# SignalAndKeyController.net
KiCad netlist of a schematic drawn in Altium Designer
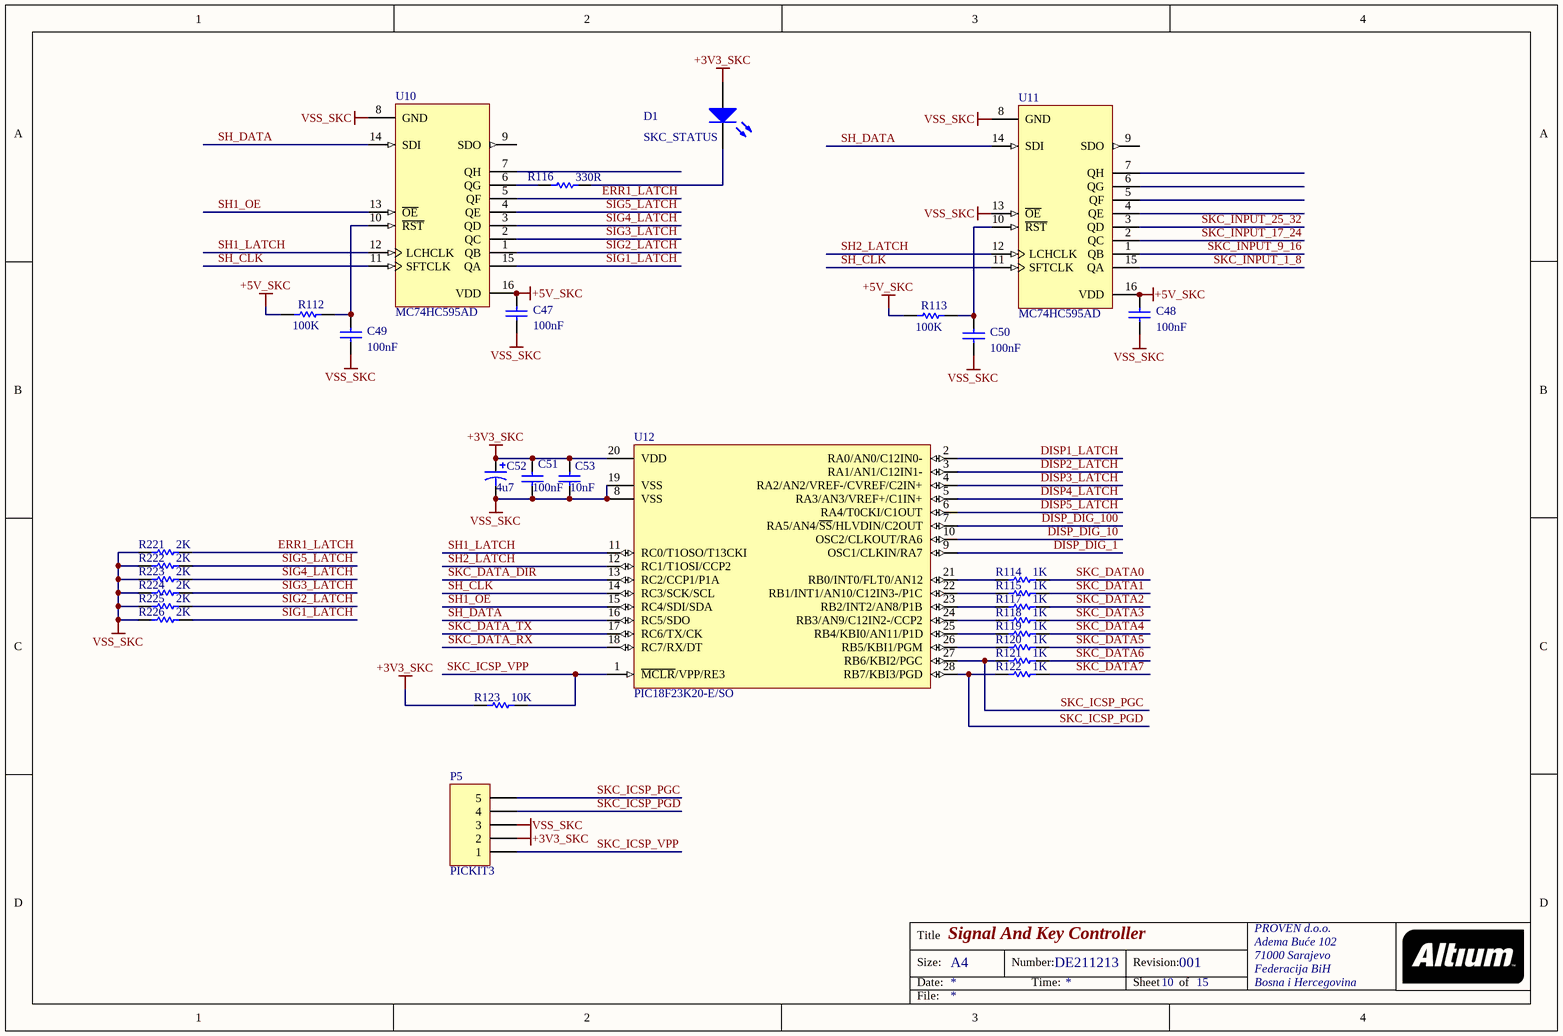
[diagram p0: SignalAndKeyController.SchDoc]

(export (version "E")
  (design (tool "Eeschema 10.0.6"))
  (components
    (comp (ref "C47")
      (value "100nF")
      (footprint "1206")
      (description "Ceramic Chip Capacitor - Standard")
      (fields (field (name "PUBLISHER") "Altium Limited"))
      (libsource (lib "KEMET Chip Capacitor") (part "C1206"))
    )
    (comp (ref "C48")
      (value "100nF")
      (footprint "1206")
      (description "Ceramic Chip Capacitor - Standard")
      (fields (field (name "PUBLISHER") "Altium Limited"))
      (libsource (lib "KEMET Chip Capacitor") (part "C1206"))
    )
    (comp (ref "C49")
      (value "100nF")
      (footprint "1206")
      (description "Ceramic Chip Capacitor - Standard")
      (fields (field (name "PUBLISHER") "Altium Limited"))
      (libsource (lib "KEMET Chip Capacitor") (part "C1206"))
    )
    (comp (ref "C50")
      (value "100nF")
      (footprint "1206")
      (description "Ceramic Chip Capacitor - Standard")
      (fields (field (name "PUBLISHER") "Altium Limited"))
      (libsource (lib "KEMET Chip Capacitor") (part "C1206"))
    )
    (comp (ref "C51")
      (value "100nF")
      (footprint "1206")
      (description "Ceramic Chip Capacitor - Standard")
      (fields (field (name "PUBLISHER") "Altium Limited"))
      (libsource (lib "KEMET Chip Capacitor") (part "C1206"))
    )
    (comp (ref "C52")
      (value "4u7")
      (footprint "C")
      (description "Solid Aluminum Capacitor with Organic Semiconductor Electrolyte: 4.7uF, 25V, Bulk Pack")
      (fields (field (name "PUBLISHER") "Altium Limited"))
      (libsource (lib "Vishay Electrolytic Radial-Lead Capacitor") (part "94SC475X0025CBP"))
    )
    (comp (ref "C53")
      (value "10nF")
      (footprint "0805")
      (description "Ceramic Chip Capacitor - Standard")
      (fields (field (name "PUBLISHER") "Altium Limited"))
      (libsource (lib "KEMET Chip Capacitor") (part "C0805"))
    )
    (comp (ref "D1")
      (value "SKC_STATUS")
      (footprint "2.0X1.25X0.8")
      (description "SMT Top Mount Chip LED, Amber")
      (fields (field (name "PUBLISHER") "Altium Limited"))
      (libsource (lib "Avago Optoelectronic LED") (part "HSMA-S670"))
    )
    (comp (ref "P5")
      (value "PICKIT3")
      (footprint "HDR1X5")
      (description "Header, 5-Pin")
      (fields (field (name "PUBLISHER") "Altium Limited"))
      (libsource (lib "Miscellaneous Connectors") (part "Header 5"))
    )
    (comp (ref "R112")
      (value "100K")
      (footprint "ERA-0603")
      (fields (field (name "PUBLISHER") "Altium Limited"))
      (libsource (lib "Panasonic Resistor") (part "ERA3Y"))
    )
    (comp (ref "R113")
      (value "100K")
      (footprint "ERA-0603")
      (fields (field (name "PUBLISHER") "Altium Limited"))
      (libsource (lib "Panasonic Resistor") (part "ERA3Y"))
    )
    (comp (ref "R114")
      (value "1K")
      (footprint "ERA-0603")
      (fields (field (name "PUBLISHER") "Altium Limited"))
      (libsource (lib "Panasonic Resistor") (part "ERA3Y"))
    )
    (comp (ref "R115")
      (value "1K")
      (footprint "ERA-0603")
      (fields (field (name "PUBLISHER") "Altium Limited"))
      (libsource (lib "Panasonic Resistor") (part "ERA3Y"))
    )
    (comp (ref "R116")
      (value "330R")
      (footprint "ERA-0603")
      (fields (field (name "PUBLISHER") "Altium Limited"))
      (libsource (lib "Panasonic Resistor") (part "ERA3Y"))
    )
    (comp (ref "R117")
      (value "1K")
      (footprint "ERA-0603")
      (fields (field (name "PUBLISHER") "Altium Limited"))
      (libsource (lib "Panasonic Resistor") (part "ERA3Y"))
    )
    (comp (ref "R118")
      (value "1K")
      (footprint "ERA-0603")
      (fields (field (name "PUBLISHER") "Altium Limited"))
      (libsource (lib "Panasonic Resistor") (part "ERA3Y"))
    )
    (comp (ref "R119")
      (value "1K")
      (footprint "ERA-0603")
      (fields (field (name "PUBLISHER") "Altium Limited"))
      (libsource (lib "Panasonic Resistor") (part "ERA3Y"))
    )
    (comp (ref "R120")
      (value "1K")
      (footprint "ERA-0603")
      (fields (field (name "PUBLISHER") "Altium Limited"))
      (libsource (lib "Panasonic Resistor") (part "ERA3Y"))
    )
    (comp (ref "R121")
      (value "1K")
      (footprint "ERA-0603")
      (fields (field (name "PUBLISHER") "Altium Limited"))
      (libsource (lib "Panasonic Resistor") (part "ERA3Y"))
    )
    (comp (ref "R122")
      (value "1K")
      (footprint "ERA-0603")
      (fields (field (name "PUBLISHER") "Altium Limited"))
      (libsource (lib "Panasonic Resistor") (part "ERA3Y"))
    )
    (comp (ref "R123")
      (value "10K")
      (footprint "ERA-0603")
      (fields (field (name "PUBLISHER") "Altium Limited"))
      (libsource (lib "Panasonic Resistor") (part "ERA3Y"))
    )
    (comp (ref "R221")
      (value "2K")
      (footprint "ERA-0603")
      (fields (field (name "PUBLISHER") "Altium Limited"))
      (libsource (lib "Panasonic Resistor") (part "ERA3Y"))
    )
    (comp (ref "R222")
      (value "2K")
      (footprint "ERA-0603")
      (fields (field (name "PUBLISHER") "Altium Limited"))
      (libsource (lib "Panasonic Resistor") (part "ERA3Y"))
    )
    (comp (ref "R223")
      (value "2K")
      (footprint "ERA-0603")
      (fields (field (name "PUBLISHER") "Altium Limited"))
      (libsource (lib "Panasonic Resistor") (part "ERA3Y"))
    )
    (comp (ref "R224")
      (value "2K")
      (footprint "ERA-0603")
      (fields (field (name "PUBLISHER") "Altium Limited"))
      (libsource (lib "Panasonic Resistor") (part "ERA3Y"))
    )
    (comp (ref "R225")
      (value "2K")
      (footprint "ERA-0603")
      (fields (field (name "PUBLISHER") "Altium Limited"))
      (libsource (lib "Panasonic Resistor") (part "ERA3Y"))
    )
    (comp (ref "R226")
      (value "2K")
      (footprint "ERA-0603")
      (fields (field (name "PUBLISHER") "Altium Limited"))
      (libsource (lib "Panasonic Resistor") (part "ERA3Y"))
    )
    (comp (ref "U10")
      (value "MC74HC595AD")
      (footprint "751B-05_N")
      (description "8-Bit Serial-Input/Serial or Prallel-Output Shift Register with Latched 3-State Outputs")
      (fields (field (name "PUBLISHER") "Altium Limited"))
      (libsource (lib "ON Semi Logic Register") (part "MC74HC595AD"))
    )
    (comp (ref "U11")
      (value "MC74HC595AD")
      (footprint "751B-05_N")
      (description "8-Bit Serial-Input/Serial or Prallel-Output Shift Register with Latched 3-State Outputs")
      (fields (field (name "PUBLISHER") "Altium Limited"))
      (libsource (lib "ON Semi Logic Register") (part "MC74HC595AD"))
    )
    (comp (ref "U12")
      (value "PIC18F23K20-E/SO")
      (footprint "SOIC-SO28_N")
      (description "Flash Microcontroller with nanoWatt XLP Technology, 28-pin SOIC, Extended Temperature")
      (fields (field (name "PUBLISHER") "Altium Limited"))
      (libsource (lib "Microchip Microcontroller 8-Bit PIC18") (part "PIC18F23K20-E/SO"))
    )
  )
  (nets
    (net (code "1") (name "+3V3_SKC") (class "Default")
      (node (ref "C51") (pin "2") (pinfunction "2_2") (pintype "passive"))
      (node (ref "C52") (pin "1") (pinfunction "1_1") (pintype "passive"))
      (node (ref "C53") (pin "2") (pinfunction "2_2") (pintype "passive"))
      (node (ref "D1") (pin "1") (pinfunction "A_1") (pintype "passive"))
      (node (ref "P5") (pin "2") (pinfunction "2_2") (pintype "passive"))
      (node (ref "R123") (pin "1") (pinfunction "1_1") (pintype "passive"))
      (node (ref "U12") (pin "20") (pinfunction "VDD_20") (pintype "power_in"))
    )
    (net (code "2") (name "+5V_SKC") (class "Default")
      (node (ref "C47") (pin "2") (pinfunction "2_2") (pintype "passive"))
      (node (ref "C48") (pin "2") (pinfunction "2_2") (pintype "passive"))
      (node (ref "R112") (pin "1") (pinfunction "1_1") (pintype "passive"))
      (node (ref "R113") (pin "1") (pinfunction "1_1") (pintype "passive"))
      (node (ref "U10") (pin "16") (pinfunction "VDD_16") (pintype "power_in"))
      (node (ref "U11") (pin "16") (pinfunction "VDD_16") (pintype "power_in"))
    )
    (net (code "3") (name "/DISP1_LATCH") (class "Default")
      (node (ref "U12") (pin "2") (pinfunction "RA0/AN0/C12IN0-_2") (pintype "bidirectional"))
    )
    (net (code "4") (name "/DISP2_LATCH") (class "Default")
      (node (ref "U12") (pin "3") (pinfunction "RA1/AN1/C12IN1-_3") (pintype "bidirectional"))
    )
    (net (code "5") (name "/DISP3_LATCH") (class "Default")
      (node (ref "U12") (pin "4") (pinfunction "RA2/AN2/VREF-/CVREF/C2IN+_4") (pintype "bidirectional"))
    )
    (net (code "6") (name "/DISP4_LATCH") (class "Default")
      (node (ref "U12") (pin "5") (pinfunction "RA3/AN3/VREF+/C1IN+_5") (pintype "bidirectional"))
    )
    (net (code "7") (name "/DISP5_LATCH") (class "Default")
      (node (ref "U12") (pin "6") (pinfunction "RA4/T0CKI/C1OUT_6") (pintype "bidirectional"))
    )
    (net (code "8") (name "/DISP_DIG_1") (class "Default")
      (node (ref "U12") (pin "9") (pinfunction "OSC1/CLKIN/RA7_9") (pintype "bidirectional"))
    )
    (net (code "9") (name "/DISP_DIG_10") (class "Default")
      (node (ref "U12") (pin "10") (pinfunction "OSC2/CLKOUT/RA6_10") (pintype "bidirectional"))
    )
    (net (code "10") (name "/DISP_DIG_100") (class "Default")
      (node (ref "U12") (pin "7") (pinfunction "RA5/AN4/~{SS}/HLVDIN/C2OUT_7") (pintype "bidirectional"))
    )
    (net (code "11") (name "/ERR1_LATCH") (class "Default")
      (node (ref "R221") (pin "1") (pinfunction "1_1") (pintype "passive"))
      (node (ref "U10") (pin "5") (pinfunction "QF_5") (pintype "tri_state"))
    )
    (net (code "12") (name "/SH1_LATCH") (class "Default")
      (node (ref "U10") (pin "12") (pinfunction "LCHCLK_12") (pintype "input"))
      (node (ref "U12") (pin "11") (pinfunction "RC0/T1OSO/T13CKI_11") (pintype "bidirectional"))
    )
    (net (code "13") (name "/SH1_OE") (class "Default")
      (node (ref "U10") (pin "13") (pinfunction "~{OE}_13") (pintype "input"))
      (node (ref "U12") (pin "15") (pinfunction "RC4/SDI/SDA_15") (pintype "bidirectional"))
    )
    (net (code "14") (name "/SH2_LATCH") (class "Default")
      (node (ref "U11") (pin "12") (pinfunction "LCHCLK_12") (pintype "input"))
      (node (ref "U12") (pin "12") (pinfunction "RC1/T1OSI/CCP2_12") (pintype "bidirectional"))
    )
    (net (code "15") (name "/SH_CLK") (class "Default")
      (node (ref "U10") (pin "11") (pinfunction "SFTCLK_11") (pintype "input"))
      (node (ref "U11") (pin "11") (pinfunction "SFTCLK_11") (pintype "input"))
      (node (ref "U12") (pin "14") (pinfunction "RC3/SCK/SCL_14") (pintype "bidirectional"))
    )
    (net (code "16") (name "/SH_DATA") (class "Default")
      (node (ref "U10") (pin "14") (pinfunction "SDI_14") (pintype "input"))
      (node (ref "U11") (pin "14") (pinfunction "SDI_14") (pintype "input"))
      (node (ref "U12") (pin "16") (pinfunction "RC5/SDO_16") (pintype "bidirectional"))
    )
    (net (code "17") (name "/SIG1_LATCH") (class "Default")
      (node (ref "R226") (pin "1") (pinfunction "1_1") (pintype "passive"))
      (node (ref "U10") (pin "15") (pinfunction "QA_15") (pintype "tri_state"))
    )
    (net (code "18") (name "/SIG2_LATCH") (class "Default")
      (node (ref "R225") (pin "1") (pinfunction "1_1") (pintype "passive"))
      (node (ref "U10") (pin "1") (pinfunction "QB_1") (pintype "tri_state"))
    )
    (net (code "19") (name "/SIG3_LATCH") (class "Default")
      (node (ref "R224") (pin "1") (pinfunction "1_1") (pintype "passive"))
      (node (ref "U10") (pin "2") (pinfunction "QC_2") (pintype "tri_state"))
    )
    (net (code "20") (name "/SIG4_LATCH") (class "Default")
      (node (ref "R223") (pin "1") (pinfunction "1_1") (pintype "passive"))
      (node (ref "U10") (pin "3") (pinfunction "QD_3") (pintype "tri_state"))
    )
    (net (code "21") (name "/SIG5_LATCH") (class "Default")
      (node (ref "R222") (pin "1") (pinfunction "1_1") (pintype "passive"))
      (node (ref "U10") (pin "4") (pinfunction "QE_4") (pintype "tri_state"))
    )
    (net (code "22") (name "/SKC_DATA0") (class "Default")
      (node (ref "R114") (pin "2") (pinfunction "2_2") (pintype "passive"))
    )
    (net (code "23") (name "/SKC_DATA1") (class "Default")
      (node (ref "R115") (pin "2") (pinfunction "2_2") (pintype "passive"))
    )
    (net (code "24") (name "/SKC_DATA2") (class "Default")
      (node (ref "R117") (pin "2") (pinfunction "2_2") (pintype "passive"))
    )
    (net (code "25") (name "/SKC_DATA3") (class "Default")
      (node (ref "R118") (pin "2") (pinfunction "2_2") (pintype "passive"))
    )
    (net (code "26") (name "/SKC_DATA4") (class "Default")
      (node (ref "R119") (pin "2") (pinfunction "2_2") (pintype "passive"))
    )
    (net (code "27") (name "/SKC_DATA5") (class "Default")
      (node (ref "R120") (pin "2") (pinfunction "2_2") (pintype "passive"))
    )
    (net (code "28") (name "/SKC_DATA6") (class "Default")
      (node (ref "R121") (pin "2") (pinfunction "2_2") (pintype "passive"))
    )
    (net (code "29") (name "/SKC_DATA7") (class "Default")
      (node (ref "R122") (pin "2") (pinfunction "2_2") (pintype "passive"))
    )
    (net (code "30") (name "/SKC_DATA_DIR") (class "Default")
      (node (ref "U12") (pin "13") (pinfunction "RC2/CCP1/P1A_13") (pintype "bidirectional"))
    )
    (net (code "31") (name "/SKC_DATA_RX") (class "Default")
      (node (ref "U12") (pin "18") (pinfunction "RC7/RX/DT_18") (pintype "bidirectional"))
    )
    (net (code "32") (name "/SKC_DATA_TX") (class "Default")
      (node (ref "U12") (pin "17") (pinfunction "RC6/TX/CK_17") (pintype "bidirectional"))
    )
    (net (code "33") (name "/SKC_ICSP_PGC") (class "Default")
      (node (ref "P5") (pin "5") (pinfunction "5_5") (pintype "passive"))
      (node (ref "R121") (pin "1") (pinfunction "1_1") (pintype "passive"))
      (node (ref "U12") (pin "27") (pinfunction "RB6/KBI2/PGC_27") (pintype "bidirectional"))
    )
    (net (code "34") (name "/SKC_ICSP_PGD") (class "Default")
      (node (ref "P5") (pin "4") (pinfunction "4_4") (pintype "passive"))
      (node (ref "R122") (pin "1") (pinfunction "1_1") (pintype "passive"))
      (node (ref "U12") (pin "28") (pinfunction "RB7/KBI3/PGD_28") (pintype "bidirectional"))
    )
    (net (code "35") (name "/SKC_ICSP_VPP") (class "Default")
      (node (ref "P5") (pin "1") (pinfunction "1_1") (pintype "passive"))
      (node (ref "R123") (pin "2") (pinfunction "2_2") (pintype "passive"))
      (node (ref "U12") (pin "1") (pinfunction "~{MCLR}/VPP/RE3_1") (pintype "input"))
    )
    (net (code "36") (name "/SKC_INPUT_1_8") (class "Default")
      (node (ref "U11") (pin "15") (pinfunction "QA_15") (pintype "tri_state"))
    )
    (net (code "37") (name "/SKC_INPUT_9_16") (class "Default")
      (node (ref "U11") (pin "1") (pinfunction "QB_1") (pintype "tri_state"))
    )
    (net (code "38") (name "/SKC_INPUT_17_24") (class "Default")
      (node (ref "U11") (pin "2") (pinfunction "QC_2") (pintype "tri_state"))
    )
    (net (code "39") (name "/SKC_INPUT_25_32") (class "Default")
      (node (ref "U11") (pin "3") (pinfunction "QD_3") (pintype "tri_state"))
    )
    (net (code "40") (name "Net-(D1-K)") (class "Default")
      (node (ref "D1") (pin "2") (pinfunction "K_2") (pintype "passive"))
      (node (ref "R116") (pin "2") (pinfunction "2_2") (pintype "passive"))
    )
    (net (code "41") (name "Net-(U10-QG)") (class "Default")
      (node (ref "R116") (pin "1") (pinfunction "1_1") (pintype "passive"))
      (node (ref "U10") (pin "6") (pinfunction "QG_6") (pintype "tri_state"))
    )
    (net (code "42") (name "Net-(U10-~{RST})") (class "Default")
      (node (ref "C49") (pin "2") (pinfunction "2_2") (pintype "passive"))
      (node (ref "R112") (pin "2") (pinfunction "2_2") (pintype "passive"))
      (node (ref "U10") (pin "10") (pinfunction "~{RST}_10") (pintype "input"))
    )
    (net (code "43") (name "Net-(U11-~{RST})") (class "Default")
      (node (ref "C50") (pin "2") (pinfunction "2_2") (pintype "passive"))
      (node (ref "R113") (pin "2") (pinfunction "2_2") (pintype "passive"))
      (node (ref "U11") (pin "10") (pinfunction "~{RST}_10") (pintype "input"))
    )
    (net (code "44") (name "Net-(U12-RB0{slash}INT0{slash}FLT0{slash}AN12)") (class "Default")
      (node (ref "R114") (pin "1") (pinfunction "1_1") (pintype "passive"))
      (node (ref "U12") (pin "21") (pinfunction "RB0/INT0/FLT0/AN12_21") (pintype "bidirectional"))
    )
    (net (code "45") (name "Net-(U12-RB1{slash}INT1{slash}AN10{slash}C12IN3-{slash}P1C)") (class "Default")
      (node (ref "R115") (pin "1") (pinfunction "1_1") (pintype "passive"))
      (node (ref "U12") (pin "22") (pinfunction "RB1/INT1/AN10/C12IN3-/P1C_22") (pintype "bidirectional"))
    )
    (net (code "46") (name "Net-(U12-RB2{slash}INT2{slash}AN8{slash}P1B)") (class "Default")
      (node (ref "R117") (pin "1") (pinfunction "1_1") (pintype "passive"))
      (node (ref "U12") (pin "23") (pinfunction "RB2/INT2/AN8/P1B_23") (pintype "bidirectional"))
    )
    (net (code "47") (name "Net-(U12-RB3{slash}AN9{slash}C12IN2-{slash}CCP2)") (class "Default")
      (node (ref "R118") (pin "1") (pinfunction "1_1") (pintype "passive"))
      (node (ref "U12") (pin "24") (pinfunction "RB3/AN9/C12IN2-/CCP2_24") (pintype "bidirectional"))
    )
    (net (code "48") (name "Net-(U12-RB4{slash}KBI0{slash}AN11{slash}P1D)") (class "Default")
      (node (ref "R119") (pin "1") (pinfunction "1_1") (pintype "passive"))
      (node (ref "U12") (pin "25") (pinfunction "RB4/KBI0/AN11/P1D_25") (pintype "bidirectional"))
    )
    (net (code "49") (name "Net-(U12-RB5{slash}KBI1{slash}PGM)") (class "Default")
      (node (ref "R120") (pin "1") (pinfunction "1_1") (pintype "passive"))
      (node (ref "U12") (pin "26") (pinfunction "RB5/KBI1/PGM_26") (pintype "bidirectional"))
    )
    (net (code "50") (name "VSS_SKC") (class "Default")
      (node (ref "C47") (pin "1") (pinfunction "1_1") (pintype "passive"))
      (node (ref "C48") (pin "1") (pinfunction "1_1") (pintype "passive"))
      (node (ref "C49") (pin "1") (pinfunction "1_1") (pintype "passive"))
      (node (ref "C50") (pin "1") (pinfunction "1_1") (pintype "passive"))
      (node (ref "C51") (pin "1") (pinfunction "1_1") (pintype "passive"))
      (node (ref "C52") (pin "2") (pinfunction "2_2") (pintype "passive"))
      (node (ref "C53") (pin "1") (pinfunction "1_1") (pintype "passive"))
      (node (ref "P5") (pin "3") (pinfunction "3_3") (pintype "passive"))
      (node (ref "R221") (pin "2") (pinfunction "2_2") (pintype "passive"))
      (node (ref "R222") (pin "2") (pinfunction "2_2") (pintype "passive"))
      (node (ref "R223") (pin "2") (pinfunction "2_2") (pintype "passive"))
      (node (ref "R224") (pin "2") (pinfunction "2_2") (pintype "passive"))
      (node (ref "R225") (pin "2") (pinfunction "2_2") (pintype "passive"))
      (node (ref "R226") (pin "2") (pinfunction "2_2") (pintype "passive"))
      (node (ref "U10") (pin "8") (pinfunction "GND_8") (pintype "power_in"))
      (node (ref "U11") (pin "13") (pinfunction "~{OE}_13") (pintype "input"))
      (node (ref "U11") (pin "8") (pinfunction "GND_8") (pintype "power_in"))
      (node (ref "U12") (pin "19") (pinfunction "VSS_19") (pintype "power_in"))
      (node (ref "U12") (pin "8") (pinfunction "VSS_8") (pintype "power_in"))
    )
    (net (code "51") (name "unconnected-(U10-QH-Pad7)") (class "Default")
      (node (ref "U10") (pin "7") (pinfunction "QH_7") (pintype "tri_state"))
    )
    (net (code "52") (name "unconnected-(U10-SDO-Pad9)") (class "Default")
      (node (ref "U10") (pin "9") (pinfunction "SDO_9") (pintype "output"))
    )
    (net (code "53") (name "unconnected-(U11-QE-Pad4)") (class "Default")
      (node (ref "U11") (pin "4") (pinfunction "QE_4") (pintype "tri_state"))
    )
    (net (code "54") (name "unconnected-(U11-QF-Pad5)") (class "Default")
      (node (ref "U11") (pin "5") (pinfunction "QF_5") (pintype "tri_state"))
    )
    (net (code "55") (name "unconnected-(U11-QG-Pad6)") (class "Default")
      (node (ref "U11") (pin "6") (pinfunction "QG_6") (pintype "tri_state"))
    )
    (net (code "56") (name "unconnected-(U11-QH-Pad7)") (class "Default")
      (node (ref "U11") (pin "7") (pinfunction "QH_7") (pintype "tri_state"))
    )
    (net (code "57") (name "unconnected-(U11-SDO-Pad9)") (class "Default")
      (node (ref "U11") (pin "9") (pinfunction "SDO_9") (pintype "output"))
    )
  )
)
